# Microcontroller.net
KiCad netlist of a schematic drawn in Altium Designer
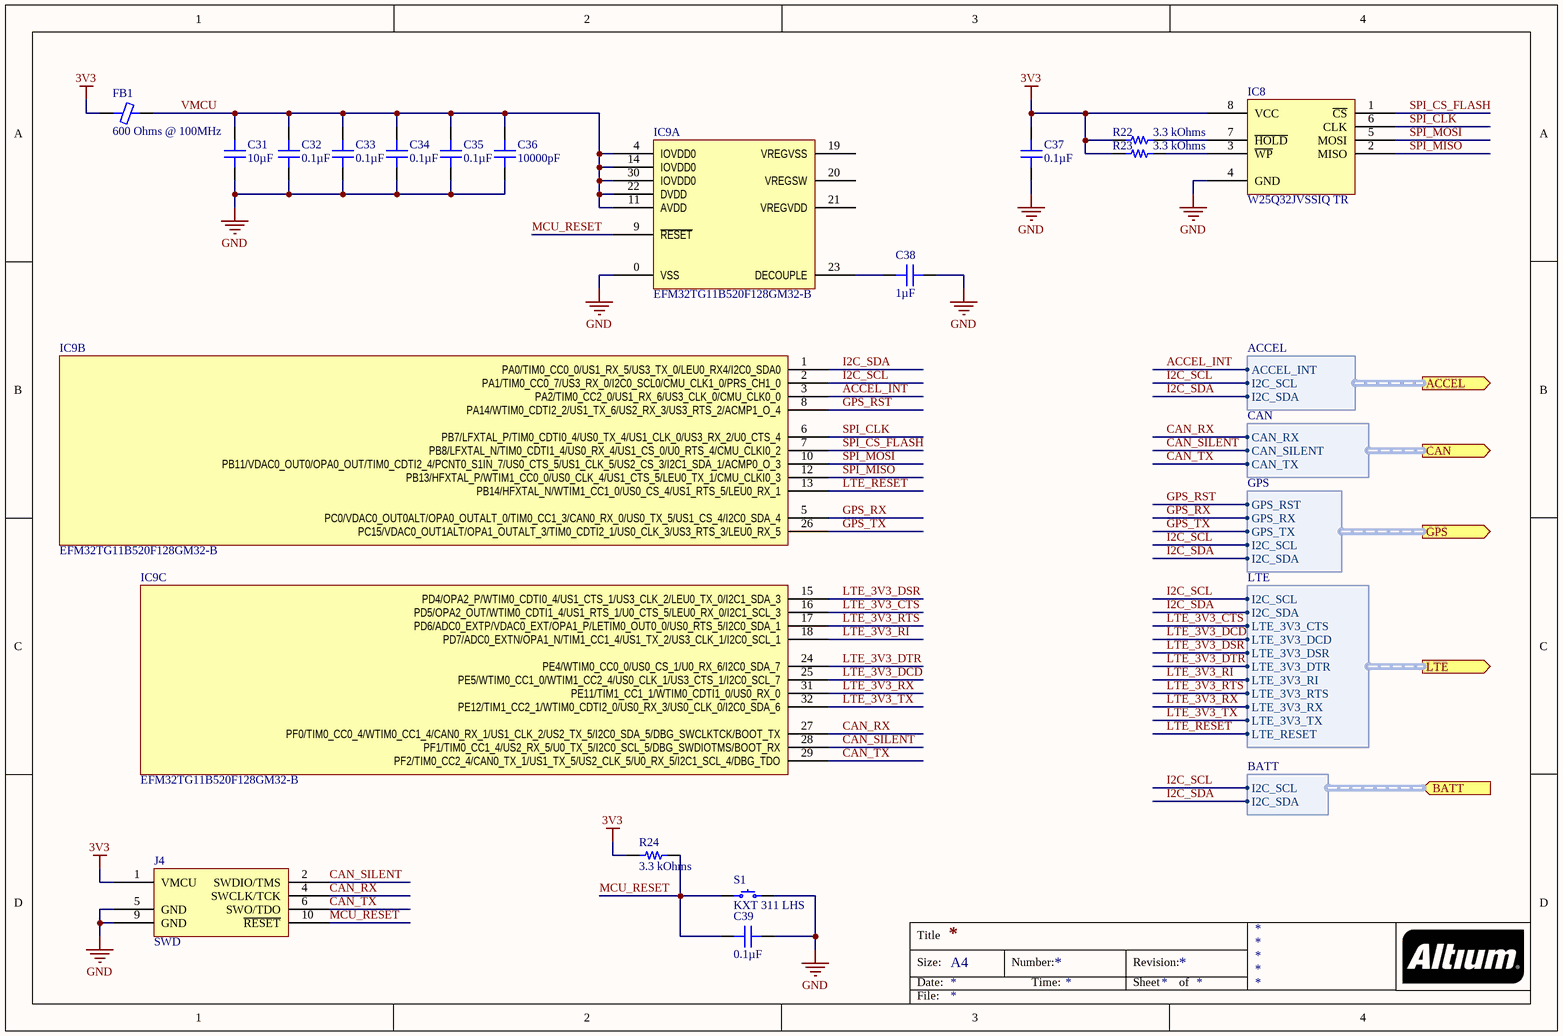
[diagram p0: Microcontroller.SchDoc]

(export (version "E")
  (design (tool "Eeschema 10.0.6"))
  (components
    (comp (ref "C31")
      (value "10µF")
      (footprint "CAP 0402_1005")
      (description "CAP CER 10UF 6.3V X5R 0402")
      (fields
        (field (name "PART NUMBER") "GRM155R60J106ME15D")
        (field (name "MANUFACTURER") "Murata Electronics")
      )
      (libsource (lib "Celestial Altium Library - altium_library") (part "Capacitor"))
    )
    (comp (ref "C32")
      (value "0.1µF")
      (footprint "CAP 0201_0603")
      (description "CAP CER 0.1UF 16V X5R 0201")
      (fields
        (field (name "PART NUMBER") "GRM033R61C104ME84D")
        (field (name "MANUFACTURER") "Murata Electronics")
      )
      (libsource (lib "Celestial Altium Library - altium_library") (part "Capacitor"))
    )
    (comp (ref "C33")
      (value "0.1µF")
      (footprint "CAP 0201_0603")
      (description "CAP CER 0.1UF 16V X5R 0201")
      (fields
        (field (name "PART NUMBER") "GRM033R61C104ME84D")
        (field (name "MANUFACTURER") "Murata Electronics")
      )
      (libsource (lib "Celestial Altium Library - altium_library") (part "Capacitor"))
    )
    (comp (ref "C34")
      (value "0.1µF")
      (footprint "CAP 0201_0603")
      (description "CAP CER 0.1UF 16V X5R 0201")
      (fields
        (field (name "PART NUMBER") "GRM033R61C104ME84D")
        (field (name "MANUFACTURER") "Murata Electronics")
      )
      (libsource (lib "Celestial Altium Library - altium_library") (part "Capacitor"))
    )
    (comp (ref "C35")
      (value "0.1µF")
      (footprint "CAP 0201_0603")
      (description "CAP CER 0.1UF 16V X5R 0201")
      (fields
        (field (name "PART NUMBER") "GRM033R61C104ME84D")
        (field (name "MANUFACTURER") "Murata Electronics")
      )
      (libsource (lib "Celestial Altium Library - altium_library") (part "Capacitor"))
    )
    (comp (ref "C36")
      (value "10000pF")
      (footprint "CAP 0201_0603")
      (description "CAP CER 10000PF 6.3V X7R 0201")
      (fields
        (field (name "PART NUMBER") "CGA1A2X7R0J103M030BA")
        (field (name "MANUFACTURER") "TDK Corporation")
      )
      (libsource (lib "Celestial Altium Library - altium_library") (part "Capacitor"))
    )
    (comp (ref "C37")
      (value "0.1µF")
      (footprint "CAP 0201_0603")
      (description "CAP CER 0.1UF 16V X5R 0201")
      (fields
        (field (name "PART NUMBER") "GRM033R61C104ME84D")
        (field (name "MANUFACTURER") "Murata Electronics")
      )
      (libsource (lib "Celestial Altium Library - altium_library") (part "Capacitor"))
    )
    (comp (ref "C38")
      (value "1µF")
      (footprint "CAP 0402_1005")
      (description "CAP CER 1UF 6.3V X6S 0402")
      (fields (field (name "PART NUMBER") "JMK105C6105KV-F") (field (name "MANUFACTURER") "Taiyo Yuden"))
      (libsource (lib "Celestial Altium Library - altium_library") (part "Capacitor"))
    )
    (comp (ref "C39")
      (value "0.1µF")
      (footprint "CAP 0201_0603")
      (description "CAP CER 0.1UF 16V X5R 0201")
      (fields
        (field (name "PART NUMBER") "GRM033R61C104ME84D")
        (field (name "MANUFACTURER") "Murata Electronics")
      )
      (libsource (lib "Celestial Altium Library - altium_library") (part "Capacitor"))
    )
    (comp (ref "FB1")
      (value "600 Ohms @ 100MHz")
      (footprint "FER 0402_1005")
      (description "FERRITE BEAD 600 OHM 0402 1LN")
      (fields
        (field (name "PART NUMBER") "BLM15PX601SZ1D")
        (field (name "MANUFACTURER") "Murata Electronics")
      )
      (libsource (lib "Celestial Altium Library - altium_library") (part "Ferrite Chip"))
    )
    (comp (ref "IC8")
      (value "W25Q32JVSSIQ TR")
      (footprint "WINBOND SOIC-8 208MIL WIDE")
      (description "IC FLASH 32M SPI 133MHZ 8SOIC")
      (fields (field (name "MANUFACTURER") "Winbond Electronics"))
      (libsource (lib "Celestial Altium Library - altium_library") (part "WINBOND FLASH SPI 8PIN"))
    )
    (comp (ref "IC9")
      (value "EFM32TG11B520F128GM32-B")
      (footprint "SI LABS QFN-32(5x5)")
      (description "LOW PWR MCU CORTEX-M0+ QFN32 128")
      (fields (field (name "MANUFACTURER") "Silicon Labs"))
      (libsource (lib "Celestial Altium Library - altium_library") (part "SI LABS EFM32TG11B5"))
    )
    (comp (ref "J4") (value "SWD") (footprint "10 Pin SWD") (libsource (lib "Useful") (part "SWD")))
    (comp (ref "R22")
      (value "3.3 kOhms")
      (footprint "RES 0201_0603")
      (description "RES SMD 3.3K OHM 1% 1/20W 0201")
      (fields
        (field (name "PART NUMBER") "ERJ-1GNF3301C")
        (field (name "MANUFACTURER") "Panasonic Electronic Components")
      )
      (libsource (lib "Celestial Altium Library - altium_library") (part "Resistor"))
    )
    (comp (ref "R23")
      (value "3.3 kOhms")
      (footprint "RES 0201_0603")
      (description "RES SMD 3.3K OHM 1% 1/20W 0201")
      (fields
        (field (name "PART NUMBER") "ERJ-1GNF3301C")
        (field (name "MANUFACTURER") "Panasonic Electronic Components")
      )
      (libsource (lib "Celestial Altium Library - altium_library") (part "Resistor"))
    )
    (comp (ref "R24")
      (value "3.3 kOhms")
      (footprint "RES 0201_0603")
      (description "RES SMD 3.3K OHM 1% 1/20W 0201")
      (fields
        (field (name "PART NUMBER") "ERJ-1GNF3301C")
        (field (name "MANUFACTURER") "Panasonic Electronic Components")
      )
      (libsource (lib "Celestial Altium Library - altium_library") (part "Resistor"))
    )
    (comp (ref "S1")
      (value "KXT 311 LHS")
      (footprint "C&K KXT3")
      (description "SWITCH TACTILE SPST-NO 0.02A 15V")
      (fields (field (name "MANUFACTURER") "C&K"))
      (libsource (lib "Celestial Altium Library - altium_library") (part "SPST-NO 2 PIN"))
    )
  )
  (nets
    (net (code "6") (name "/ACCEL_INT") (class "Default")
      (node (ref "IC9") (pin "3") (pinfunction "PA2/TIM0_CC2_0/US1_RX_6/US3_CLK_0/CMU_CLK0_0_3") (pintype "passive"))
    )
    (net (code "7") (name "/CAN_RX") (class "Default")
      (node (ref "IC9") (pin "27") (pinfunction "PF0/TIM0_CC0_4/WTIM0_CC1_4/CAN0_RX_1/US1_CLK_2/US2_TX_5/I2C0_SDA_5/DBG_SWCLKTCK/BOOT_TX_27") (pintype "passive"))
      (node (ref "J4") (pin "4") (pinfunction "SWCLK/TCK_4") (pintype "passive"))
    )
    (net (code "8") (name "/CAN_SILENT") (class "Default")
      (node (ref "IC9") (pin "28") (pinfunction "PF1/TIM0_CC1_4/US2_RX_5/U0_TX_5/I2C0_SCL_5/DBG_SWDIOTMS/BOOT_RX_28") (pintype "passive"))
      (node (ref "J4") (pin "2") (pinfunction "SWDIO/TMS_2") (pintype "passive"))
    )
    (net (code "9") (name "/CAN_TX") (class "Default")
      (node (ref "IC9") (pin "29") (pinfunction "PF2/TIM0_CC2_4/CAN0_TX_1/US1_TX_5/US2_CLK_5/U0_RX_5/I2C1_SCL_4/DBG_TDO_29") (pintype "passive"))
      (node (ref "J4") (pin "6") (pinfunction "SWO/TDO_6") (pintype "passive"))
    )
    (net (code "10") (name "/GPS_RST") (class "Default")
      (node (ref "IC9") (pin "8") (pinfunction "PA14/WTIM0_CDTI2_2/US1_TX_6/US2_RX_3/US3_RTS_2/ACMP1_O_4_8") (pintype "passive"))
    )
    (net (code "11") (name "/GPS_RX") (class "Default")
      (node (ref "IC9") (pin "5") (pinfunction "PC0/VDAC0_OUT0ALT/OPA0_OUTALT_0/TIM0_CC1_3/CAN0_RX_0/US0_TX_5/US1_CS_4/I2C0_SDA_4_5") (pintype "passive"))
    )
    (net (code "12") (name "/GPS_TX") (class "Default")
      (node (ref "IC9") (pin "26") (pinfunction "PC15/VDAC0_OUT1ALT/OPA1_OUTALT_3/TIM0_CDTI2_1/US0_CLK_3/US3_RTS_3/LEU0_RX_5_26") (pintype "passive"))
    )
    (net (code "13") (name "/I2C_SCL") (class "Default")
      (node (ref "IC9") (pin "2") (pinfunction "PA1/TIM0_CC0_7/US3_RX_0/I2C0_SCL0/CMU_CLK1_0/PRS_CH1_0_2") (pintype "passive"))
    )
    (net (code "14") (name "/I2C_SDA") (class "Default")
      (node (ref "IC9") (pin "1") (pinfunction "PA0/TIM0_CC0_0/US1_RX_5/US3_TX_0/LEU0_RX4/I2C0_SDA0_1") (pintype "passive"))
    )
    (net (code "15") (name "/LTE_3V3_CTS") (class "Default")
      (node (ref "IC9") (pin "16") (pinfunction "PD5/OPA2_OUT/WTIM0_CDTI1_4/US1_RTS_1/U0_CTS_5/LEU0_RX_0/I2C1_SCL_3_16") (pintype "passive"))
    )
    (net (code "16") (name "/LTE_3V3_DCD") (class "Default")
      (node (ref "IC9") (pin "25") (pinfunction "PE5/WTIM0_CC1_0/WTIM1_CC2_4/US0_CLK_1/US3_CTS_1/I2C0_SCL_7_25") (pintype "passive"))
    )
    (net (code "17") (name "/LTE_3V3_DSR") (class "Default")
      (node (ref "IC9") (pin "15") (pinfunction "PD4/OPA2_P/WTIM0_CDTI0_4/US1_CTS_1/US3_CLK_2/LEU0_TX_0/I2C1_SDA_3_15") (pintype "passive"))
    )
    (net (code "18") (name "/LTE_3V3_DTR") (class "Default")
      (node (ref "IC9") (pin "24") (pinfunction "PE4/WTIM0_CC0_0/US0_CS_1/U0_RX_6/I2C0_SDA_7_24") (pintype "passive"))
    )
    (net (code "19") (name "/LTE_3V3_RI") (class "Default")
      (node (ref "IC9") (pin "18") (pinfunction "PD7/ADC0_EXTN/OPA1_N/TIM1_CC1_4/US1_TX_2/US3_CLK_1/I2C0_SCL_1_18") (pintype "passive"))
    )
    (net (code "20") (name "/LTE_3V3_RTS") (class "Default")
      (node (ref "IC9") (pin "17") (pinfunction "PD6/ADC0_EXTP/VDAC0_EXT/OPA1_P/LETIM0_OUT0_0/US0_RTS_5/I2C0_SDA_1_17") (pintype "passive"))
    )
    (net (code "21") (name "/LTE_3V3_RX") (class "Default")
      (node (ref "IC9") (pin "31") (pinfunction "PE11/TIM1_CC1_1/WTIM0_CDTI1_0/US0_RX_0_31") (pintype "passive"))
    )
    (net (code "22") (name "/LTE_3V3_TX") (class "Default")
      (node (ref "IC9") (pin "32") (pinfunction "PE12/TIM1_CC2_1/WTIM0_CDTI2_0/US0_RX_3/US0_CLK_0/I2C0_SDA_6_32") (pintype "passive"))
    )
    (net (code "23") (name "/LTE_RESET") (class "Default")
      (node (ref "IC9") (pin "13") (pinfunction "PB14/HFXTAL_N/WTIM1_CC1_0/US0_CS_4/US1_RTS_5/LEU0_RX_1_13") (pintype "passive"))
    )
    (net (code "24") (name "/MCU_RESET") (class "Default")
      (node (ref "C39") (pin "2") (pinfunction "2_2") (pintype "passive"))
      (node (ref "IC9") (pin "9") (pinfunction "~{RESET}_9") (pintype "passive"))
      (node (ref "J4") (pin "10") (pinfunction "~{RESET}_10") (pintype "passive"))
      (node (ref "R24") (pin "1") (pinfunction "1_1") (pintype "passive"))
      (node (ref "S1") (pin "1") (pinfunction "1_1") (pintype "passive"))
    )
    (net (code "25") (name "/SPI_CLK") (class "Default")
      (node (ref "IC8") (pin "6") (pinfunction "CLK_6") (pintype "passive"))
      (node (ref "IC9") (pin "6") (pinfunction "PB7/LFXTAL_P/TIM0_CDTI0_4/US0_TX_4/US1_CLK_0/US3_RX_2/U0_CTS_4_6") (pintype "passive"))
    )
    (net (code "26") (name "/SPI_CS_FLASH") (class "Default")
      (node (ref "IC8") (pin "1") (pinfunction "~{CS}_1") (pintype "passive"))
      (node (ref "IC9") (pin "7") (pinfunction "PB8/LFXTAL_N/TIM0_CDTI1_4/US0_RX_4/US1_CS_0/U0_RTS_4/CMU_CLKI0_2_7") (pintype "passive"))
    )
    (net (code "27") (name "/SPI_MISO") (class "Default")
      (node (ref "IC8") (pin "2") (pinfunction "MISO_2") (pintype "passive"))
      (node (ref "IC9") (pin "12") (pinfunction "PB13/HFXTAL_P/WTIM1_CC0_0/US0_CLK_4/US1_CTS_5/LEU0_TX_1/CMU_CLKI0_3_12") (pintype "passive"))
    )
    (net (code "28") (name "/SPI_MOSI") (class "Default")
      (node (ref "IC8") (pin "5") (pinfunction "MOSI_5") (pintype "passive"))
      (node (ref "IC9") (pin "10") (pinfunction "PB11/VDAC0_OUT0/OPA0_OUT/TIM0_CDTI2_4/PCNT0_S1IN_7/US0_CTS_5/US1_CLK_5/US2_CS_3/I2C1_SDA_1/ACMP0_O_3_10") (pintype "passive"))
    )
    (net (code "29") (name "/VMCU") (class "Default")
      (node (ref "C31") (pin "2") (pinfunction "2_2") (pintype "passive"))
      (node (ref "C32") (pin "2") (pinfunction "2_2") (pintype "passive"))
      (node (ref "C33") (pin "2") (pinfunction "2_2") (pintype "passive"))
      (node (ref "C34") (pin "2") (pinfunction "2_2") (pintype "passive"))
      (node (ref "C35") (pin "2") (pinfunction "2_2") (pintype "passive"))
      (node (ref "C36") (pin "2") (pinfunction "2_2") (pintype "passive"))
      (node (ref "FB1") (pin "2") (pinfunction "2_2") (pintype "passive"))
      (node (ref "IC9") (pin "11") (pinfunction "AVDD_11") (pintype "passive"))
      (node (ref "IC9") (pin "14") (pinfunction "IOVDD0_14") (pintype "passive"))
      (node (ref "IC9") (pin "22") (pinfunction "DVDD_22") (pintype "passive"))
      (node (ref "IC9") (pin "30") (pinfunction "IOVDD0_30") (pintype "passive"))
      (node (ref "IC9") (pin "4") (pinfunction "IOVDD0_4") (pintype "passive"))
    )
    (net (code "35") (name "3V3") (class "Default")
      (node (ref "C37") (pin "2") (pinfunction "2_2") (pintype "passive"))
      (node (ref "FB1") (pin "1") (pinfunction "1_1") (pintype "passive"))
      (node (ref "IC8") (pin "8") (pinfunction "VCC_8") (pintype "passive"))
      (node (ref "J4") (pin "1") (pinfunction "VMCU_1") (pintype "passive"))
      (node (ref "R22") (pin "2") (pinfunction "2_2") (pintype "passive"))
      (node (ref "R23") (pin "2") (pinfunction "2_2") (pintype "passive"))
      (node (ref "R24") (pin "2") (pinfunction "2_2") (pintype "passive"))
    )
    (net (code "36") (name "GND") (class "Default")
      (node (ref "C31") (pin "1") (pinfunction "1_1") (pintype "passive"))
      (node (ref "C32") (pin "1") (pinfunction "1_1") (pintype "passive"))
      (node (ref "C33") (pin "1") (pinfunction "1_1") (pintype "passive"))
      (node (ref "C34") (pin "1") (pinfunction "1_1") (pintype "passive"))
      (node (ref "C35") (pin "1") (pinfunction "1_1") (pintype "passive"))
      (node (ref "C36") (pin "1") (pinfunction "1_1") (pintype "passive"))
      (node (ref "C37") (pin "1") (pinfunction "1_1") (pintype "passive"))
      (node (ref "C38") (pin "2") (pinfunction "2_2") (pintype "passive"))
      (node (ref "C39") (pin "1") (pinfunction "1_1") (pintype "passive"))
      (node (ref "IC8") (pin "4") (pinfunction "GND_4") (pintype "passive"))
      (node (ref "IC9") (pin "0") (pinfunction "VSS_0") (pintype "passive"))
      (node (ref "J4") (pin "5") (pinfunction "GND_5") (pintype "passive"))
      (node (ref "J4") (pin "9") (pinfunction "GND_9") (pintype "passive"))
      (node (ref "S1") (pin "2") (pinfunction "2_2") (pintype "passive"))
    )
    (net (code "37") (name "Net-(IC8-~{HOLD})") (class "Default")
      (node (ref "IC8") (pin "7") (pinfunction "~{HOLD}_7") (pintype "passive"))
      (node (ref "R22") (pin "1") (pinfunction "1_1") (pintype "passive"))
    )
    (net (code "38") (name "Net-(IC8-~{WP})") (class "Default")
      (node (ref "IC8") (pin "3") (pinfunction "~{WP}_3") (pintype "passive"))
      (node (ref "R23") (pin "1") (pinfunction "1_1") (pintype "passive"))
    )
    (net (code "39") (name "Net-(IC9A-DECOUPLE)") (class "Default")
      (node (ref "C38") (pin "1") (pinfunction "1_1") (pintype "passive"))
      (node (ref "IC9") (pin "23") (pinfunction "DECOUPLE_23") (pintype "passive"))
    )
    (net (code "40") (name "unconnected-(IC9A-VREGSW-Pad20)") (class "Default")
      (node (ref "IC9") (pin "20") (pinfunction "VREGSW_20") (pintype "passive"))
    )
    (net (code "41") (name "unconnected-(IC9A-VREGVDD-Pad21)") (class "Default")
      (node (ref "IC9") (pin "21") (pinfunction "VREGVDD_21") (pintype "passive"))
    )
    (net (code "42") (name "unconnected-(IC9A-VREGVSS-Pad19)") (class "Default")
      (node (ref "IC9") (pin "19") (pinfunction "VREGVSS_19") (pintype "passive"))
    )
  )
)
